# Qwiic_Joystick.net
KiCad netlist of a schematic drawn in EAGLE
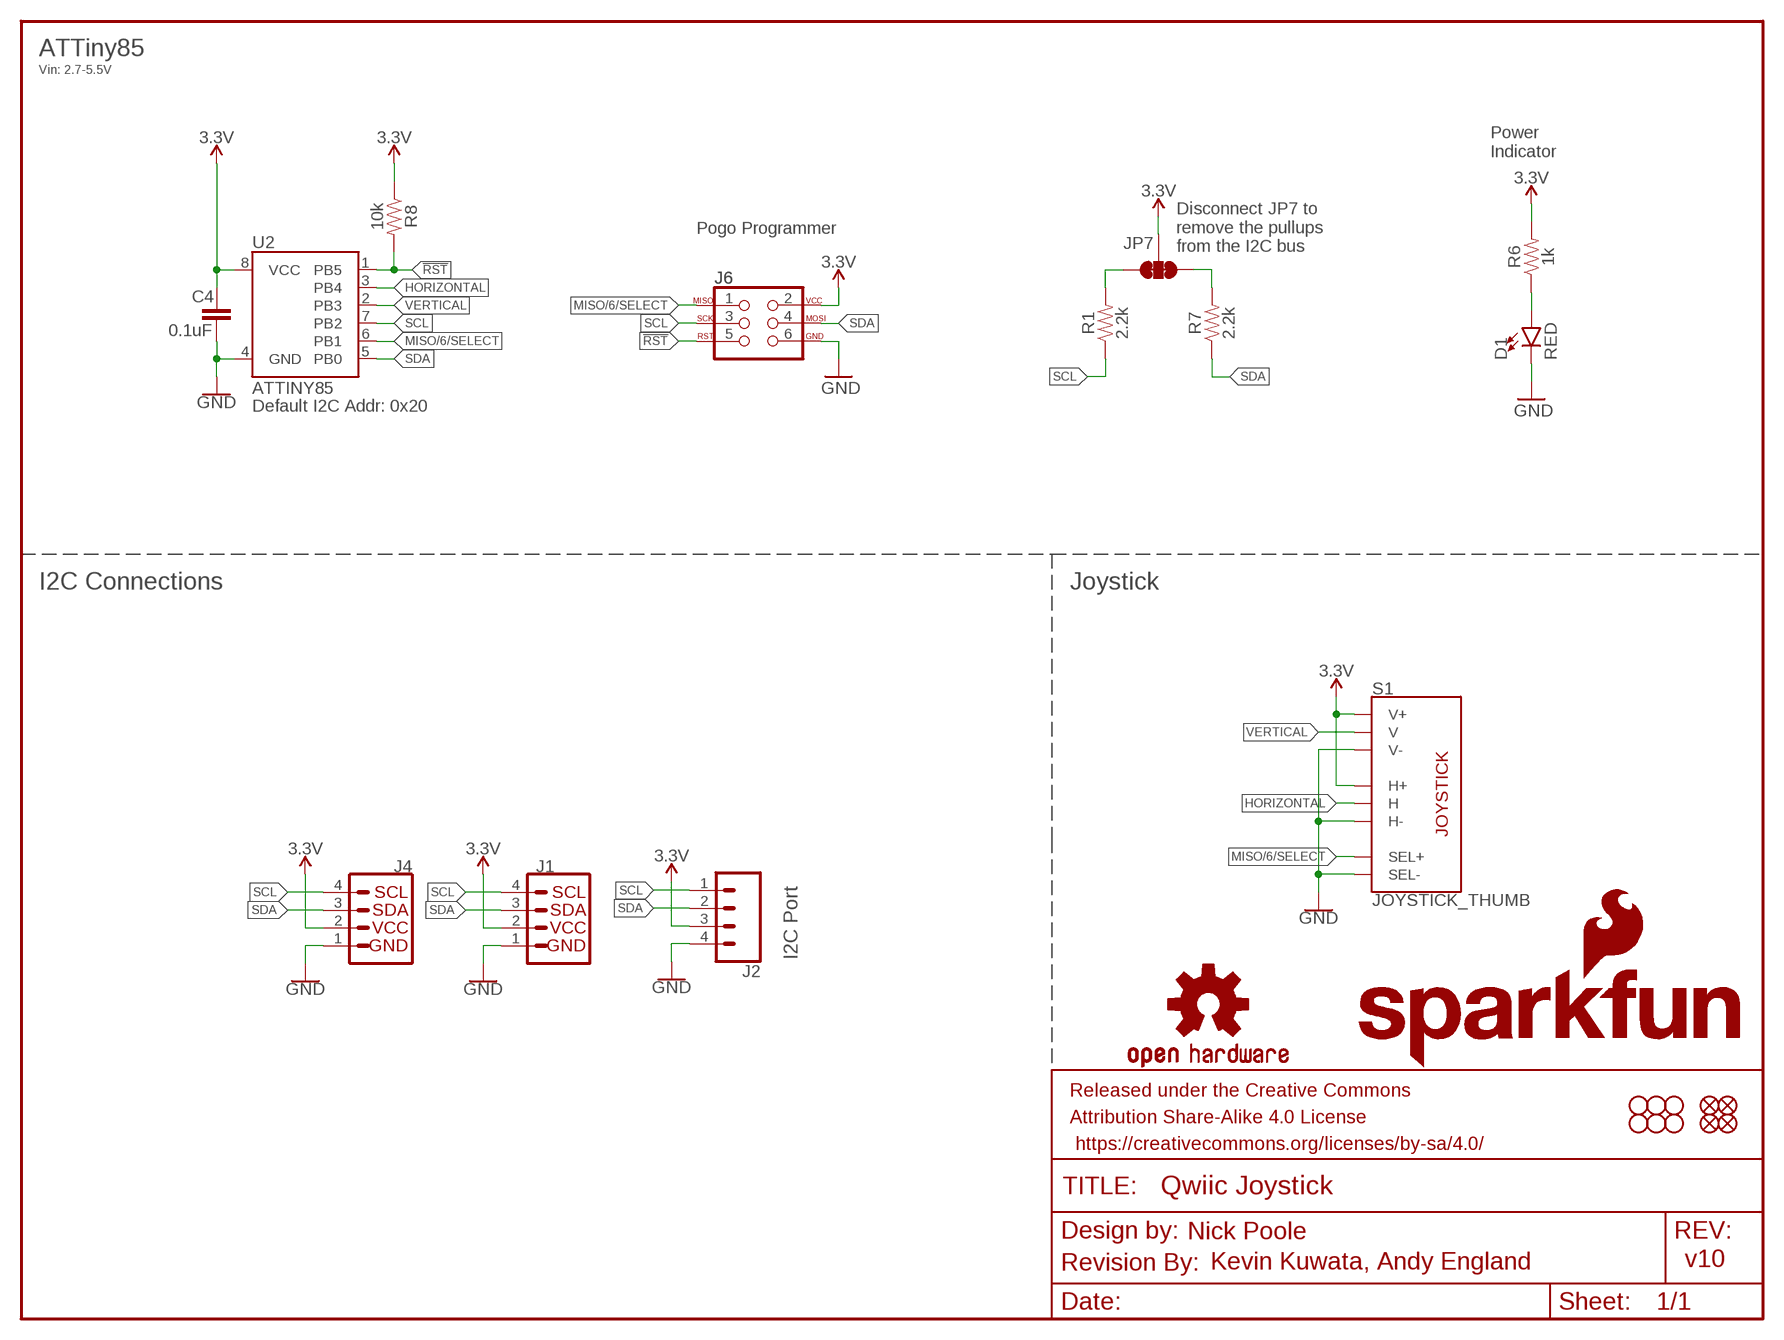
[diagram p0: schematic, sheet 1]

(export (version "E")
  (design (tool "Eeschema 10.0.6"))
  (components
    (comp (ref "C4")
      (value "0.1uF")
      (footprint "eagle-import:0603")
      (libsource (lib "eagle-import") (part "0.1UF-0603-25V-(+80/-20%)"))
    )
    (comp (ref "D1")
      (value "RED")
      (footprint "eagle-import:LED-0603")
      (libsource (lib "eagle-import") (part "LED-RED0603"))
    )
    (comp (ref "FRAME1")
      (value "FRAME-LETTER")
      (footprint "eagle-import:CREATIVE_COMMONS")
      (libsource (lib "eagle-import") (part "FRAME-LETTER"))
    )
    (comp (ref "H1")
      (value "STAND-OFF")
      (footprint "eagle-import:STAND-OFF")
      (libsource (lib "eagle-import") (part "STAND-OFF"))
    )
    (comp (ref "H2")
      (value "STAND-OFF")
      (footprint "eagle-import:STAND-OFF")
      (libsource (lib "eagle-import") (part "STAND-OFF"))
    )
    (comp (ref "H3")
      (value "STAND-OFF")
      (footprint "eagle-import:STAND-OFF")
      (libsource (lib "eagle-import") (part "STAND-OFF"))
    )
    (comp (ref "H4")
      (value "STAND-OFF")
      (footprint "eagle-import:STAND-OFF")
      (libsource (lib "eagle-import") (part "STAND-OFF"))
    )
    (comp (ref "H5")
      (value "STAND-OFF")
      (footprint "eagle-import:STAND-OFF")
      (libsource (lib "eagle-import") (part "STAND-OFF"))
    )
    (comp (ref "H6")
      (value "STAND-OFF")
      (footprint "eagle-import:STAND-OFF")
      (libsource (lib "eagle-import") (part "STAND-OFF"))
    )
    (comp (ref "J1")
      (value "QWIIC_CONNECTORJS-1MM")
      (footprint "eagle-import:1X04_1MM_RA")
      (libsource (lib "eagle-import") (part "QWIIC_CONNECTORJS-1MM"))
    )
    (comp (ref "J2")
      (value "CONN_041X04_NO_SILK")
      (footprint "eagle-import:1X04_NO_SILK")
      (libsource (lib "eagle-import") (part "CONN_041X04_NO_SILK"))
    )
    (comp (ref "J4")
      (value "QWIIC_CONNECTORJS-1MM")
      (footprint "eagle-import:1X04_1MM_RA")
      (libsource (lib "eagle-import") (part "QWIIC_CONNECTORJS-1MM"))
    )
    (comp (ref "J6")
      (value "AVR_SPI_PROG_3X2TESTPOINTS")
      (footprint "eagle-import:2X3_TEST_POINTS")
      (libsource (lib "eagle-import") (part "AVR_SPI_PROG_3X2TESTPOINTS"))
    )
    (comp (ref "JP1")
      (value "FIDUCIALUFIDUCIAL")
      (footprint "eagle-import:MICRO-FIDUCIAL")
      (libsource (lib "eagle-import") (part "FIDUCIALUFIDUCIAL"))
    )
    (comp (ref "JP2")
      (value "FIDUCIALUFIDUCIAL")
      (footprint "eagle-import:MICRO-FIDUCIAL")
      (libsource (lib "eagle-import") (part "FIDUCIALUFIDUCIAL"))
    )
    (comp (ref "JP3")
      (value "FIDUCIALUFIDUCIAL")
      (footprint "eagle-import:MICRO-FIDUCIAL")
      (libsource (lib "eagle-import") (part "FIDUCIALUFIDUCIAL"))
    )
    (comp (ref "JP6")
      (value "FIDUCIALUFIDUCIAL")
      (footprint "eagle-import:MICRO-FIDUCIAL")
      (libsource (lib "eagle-import") (part "FIDUCIALUFIDUCIAL"))
    )
    (comp (ref "JP7")
      (value "JUMPER-SMT_3_2-NC_TRACE_NO-SILK")
      (footprint "eagle-import:SMT-JUMPER_3_2-NC_TRACE_NO-SILK")
      (libsource (lib "eagle-import") (part "JUMPER-SMT_3_2-NC_TRACE_NO-SILK"))
    )
    (comp (ref "LOGO1")
      (value "OSHW-LOGOMINI")
      (footprint "eagle-import:OSHW-LOGO-MINI")
      (libsource (lib "eagle-import") (part "OSHW-LOGOMINI"))
    )
    (comp (ref "LOGO2")
      (value "REVISION")
      (footprint "eagle-import:REVISION")
      (libsource (lib "eagle-import") (part "REVISION"))
    )
    (comp (ref "R1")
      (value "2.2k")
      (footprint "eagle-import:0603")
      (libsource (lib "eagle-import") (part "2.2KOHM-0603-1/10W-1%"))
    )
    (comp (ref "R6")
      (value "1k")
      (footprint "eagle-import:0603")
      (libsource (lib "eagle-import") (part "1KOHM-0603-1/10W-1%"))
    )
    (comp (ref "R7")
      (value "2.2k")
      (footprint "eagle-import:0603")
      (libsource (lib "eagle-import") (part "2.2KOHM-0603-1/10W-1%"))
    )
    (comp (ref "R8")
      (value "10k")
      (footprint "eagle-import:0603")
      (libsource (lib "eagle-import") (part "10KOHM-0603-1/10W-1%"))
    )
    (comp (ref "S1")
      (value "JOYSTICK_THUMB")
      (footprint "eagle-import:JOYSTICK")
      (libsource (lib "eagle-import") (part "JOYSTICK_THUMB"))
    )
    (comp (ref "U$1")
      (value "SFE_LOGO_NAME_FLAME.1_INCH")
      (footprint "eagle-import:SFE_LOGO_NAME_FLAME_.1")
      (libsource (lib "eagle-import") (part "SFE_LOGO_NAME_FLAME.1_INCH"))
    )
    (comp (ref "U$2")
      (value "SFE_LOGO_NAME_FLAME.1_INCH")
      (footprint "eagle-import:SFE_LOGO_NAME_FLAME_.1")
      (libsource (lib "eagle-import") (part "SFE_LOGO_NAME_FLAME.1_INCH"))
    )
    (comp (ref "U2")
      (value "ATTINY85")
      (footprint "eagle-import:ATTINY85")
      (libsource (lib "eagle-import") (part "ATTINY85"))
    )
  )
  (nets
    (net (code "1") (name "/~{RST}") (class "Default")
      (node (ref "J6") (pin "5") (pinfunction "5_5") (pintype "passive"))
      (node (ref "R8") (pin "2") (pinfunction "2_2") (pintype "passive"))
      (node (ref "U2") (pin "1") (pinfunction "PB5_1") (pintype "bidirectional"))
    )
    (net (code "2") (name "3.3V") (class "Default")
      (node (ref "C4") (pin "1") (pinfunction "1_1") (pintype "passive"))
      (node (ref "J1") (pin "2") (pinfunction "2_2") (pintype "power_in"))
      (node (ref "J2") (pin "3") (pinfunction "3_3") (pintype "passive"))
      (node (ref "J4") (pin "2") (pinfunction "2_2") (pintype "power_in"))
      (node (ref "J6") (pin "2") (pinfunction "2_2") (pintype "passive"))
      (node (ref "JP7") (pin "2") (pinfunction "2_2") (pintype "passive"))
      (node (ref "R6") (pin "2") (pinfunction "2_2") (pintype "passive"))
      (node (ref "R8") (pin "1") (pinfunction "1_1") (pintype "passive"))
      (node (ref "S1") (pin "H1") (pinfunction "H+_H1") (pintype "bidirectional"))
      (node (ref "S1") (pin "V1") (pinfunction "V+_V1") (pintype "bidirectional"))
      (node (ref "U2") (pin "8") (pinfunction "VCC_8") (pintype "bidirectional"))
    )
    (net (code "3") (name "GND") (class "Default")
      (node (ref "C4") (pin "2") (pinfunction "2_2") (pintype "passive"))
      (node (ref "D1") (pin "C") (pinfunction "C_C") (pintype "passive"))
      (node (ref "J1") (pin "1") (pinfunction "1_1") (pintype "power_in"))
      (node (ref "J2") (pin "4") (pinfunction "4_4") (pintype "passive"))
      (node (ref "J4") (pin "1") (pinfunction "1_1") (pintype "power_in"))
      (node (ref "J6") (pin "6") (pinfunction "6_6") (pintype "passive"))
      (node (ref "S1") (pin "B2A") (pinfunction "SEL-_B2A") (pintype "bidirectional"))
      (node (ref "S1") (pin "H3") (pinfunction "H-_H3") (pintype "bidirectional"))
      (node (ref "S1") (pin "V3") (pinfunction "V-_V3") (pintype "bidirectional"))
      (node (ref "U2") (pin "4") (pinfunction "GND_4") (pintype "bidirectional"))
    )
    (net (code "4") (name "HORIZONTAL") (class "Default")
      (node (ref "S1") (pin "H2") (pinfunction "H_H2") (pintype "bidirectional"))
      (node (ref "U2") (pin "3") (pinfunction "PB4_3") (pintype "bidirectional"))
    )
    (net (code "5") (name "MISO{slash}6{slash}SELECT") (class "Default")
      (node (ref "J6") (pin "1") (pinfunction "1_1") (pintype "passive"))
      (node (ref "S1") (pin "B1A") (pinfunction "SEL+_B1A") (pintype "bidirectional"))
      (node (ref "U2") (pin "6") (pinfunction "PB1_6") (pintype "bidirectional"))
    )
    (net (code "6") (name "Net-(D1-PadA)") (class "Default")
      (node (ref "D1") (pin "A") (pinfunction "A_A") (pintype "passive"))
      (node (ref "R6") (pin "1") (pinfunction "1_1") (pintype "passive"))
    )
    (net (code "7") (name "Net-(JP7-Pad1)") (class "Default")
      (node (ref "JP7") (pin "1") (pinfunction "1_1") (pintype "passive"))
      (node (ref "R7") (pin "2") (pinfunction "2_2") (pintype "passive"))
    )
    (net (code "8") (name "Net-(JP7-Pad3)") (class "Default")
      (node (ref "JP7") (pin "3") (pinfunction "3_3") (pintype "passive"))
      (node (ref "R1") (pin "2") (pinfunction "2_2") (pintype "passive"))
    )
    (net (code "9") (name "SCL") (class "Default")
      (node (ref "J1") (pin "4") (pinfunction "4_4") (pintype "passive"))
      (node (ref "J2") (pin "1") (pinfunction "1_1") (pintype "passive"))
      (node (ref "J4") (pin "4") (pinfunction "4_4") (pintype "passive"))
      (node (ref "J6") (pin "3") (pinfunction "3_3") (pintype "passive"))
      (node (ref "R1") (pin "1") (pinfunction "1_1") (pintype "passive"))
      (node (ref "U2") (pin "7") (pinfunction "PB2_7") (pintype "bidirectional"))
    )
    (net (code "10") (name "SDA") (class "Default")
      (node (ref "J1") (pin "3") (pinfunction "3_3") (pintype "passive"))
      (node (ref "J2") (pin "2") (pinfunction "2_2") (pintype "passive"))
      (node (ref "J4") (pin "3") (pinfunction "3_3") (pintype "passive"))
      (node (ref "J6") (pin "4") (pinfunction "4_4") (pintype "passive"))
      (node (ref "R7") (pin "1") (pinfunction "1_1") (pintype "passive"))
      (node (ref "U2") (pin "5") (pinfunction "PB0_5") (pintype "bidirectional"))
    )
    (net (code "11") (name "VERTICAL") (class "Default")
      (node (ref "S1") (pin "V2") (pinfunction "V_V2") (pintype "bidirectional"))
      (node (ref "U2") (pin "2") (pinfunction "PB3_2") (pintype "bidirectional"))
    )
  )
)
